# untitled.net
KiCad netlist of a schematic drawn in EAGLE
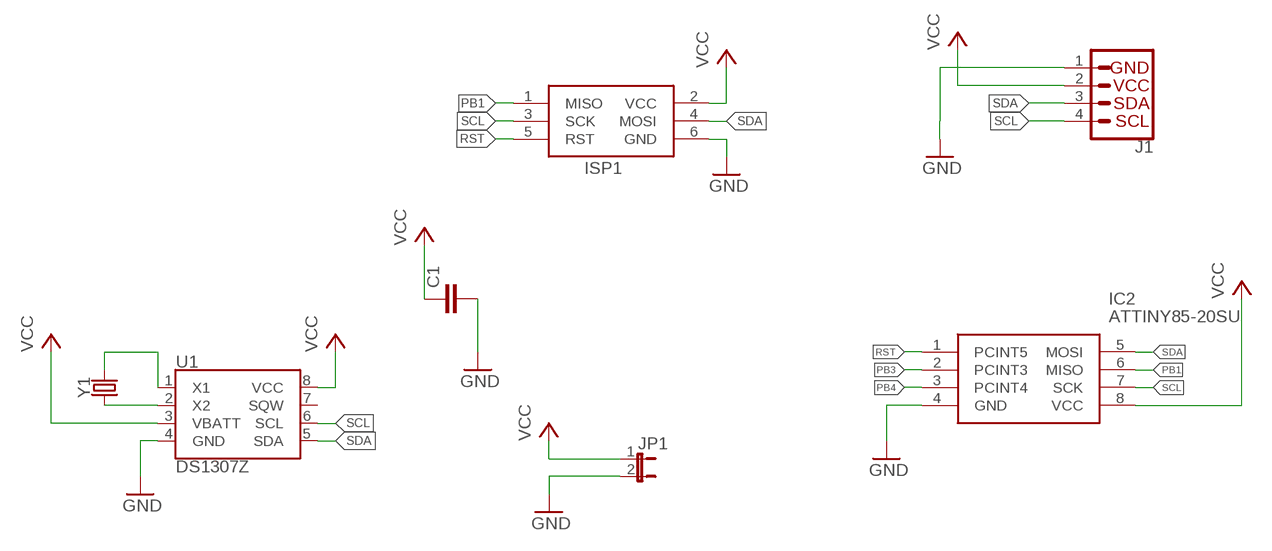
[diagram p0: schematic, sheet 1]

(export (version "E")
  (design (tool "Eeschema 10.0.6"))
  (components
    (comp (ref "C1")
      (value "C-EUC1206")
      (footprint "eagle-import:C1206")
      (libsource (lib "eagle-import") (part "C-EUC1206"))
    )
    (comp (ref "IC2")
      (value "ATTINY85-20SU")
      (footprint "eagle-import:SOT127P798X216-8N")
      (fields
        (field (name "MOUSER_PART_NUMBER") "556-ATTINY85-20SU")
        (field (name "RS_PART_NUMBER") "1331674")
      )
      (libsource (lib "eagle-import") (part "ATTINY85-20SU"))
    )
    (comp (ref "ISP1")
      (value "AVRISP-6")
      (footprint "eagle-import:AVRISP")
      (libsource (lib "eagle-import") (part "AVRISP-6"))
    )
    (comp (ref "J1")
      (value "I2C_STANDARD")
      (footprint "eagle-import:1X04")
      (libsource (lib "eagle-import") (part "I2C_STANDARD"))
    )
    (comp (ref "JP1")
      (value "JUMPER-2-OLDPTH")
      (footprint "eagle-import:1X02")
      (libsource (lib "eagle-import") (part "JUMPER-2-OLDPTH"))
    )
    (comp (ref "U1")
      (value "DS1307Z")
      (footprint "eagle-import:SO08-0.15")
      (libsource (lib "eagle-import") (part "DS1307Z"))
    )
    (comp (ref "Y1")
      (value "CRYSTALPTH-2X6")
      (footprint "eagle-import:CRYSTAL-PTH-2X6-CYL")
      (libsource (lib "eagle-import") (part "CRYSTALPTH-2X6"))
    )
  )
  (nets
    (net (code "1") (name "GND") (class "Default")
      (node (ref "C1") (pin "2") (pinfunction "2_2") (pintype "passive"))
      (node (ref "IC2") (pin "4") (pinfunction "GND_4") (pintype "power_in"))
      (node (ref "ISP1") (pin "6") (pinfunction "GND_6") (pintype "power_in"))
      (node (ref "J1") (pin "1") (pinfunction "1_1") (pintype "power_in"))
      (node (ref "JP1") (pin "2") (pinfunction "2_2") (pintype "passive"))
      (node (ref "U1") (pin "4") (pinfunction "GND_4") (pintype "bidirectional"))
    )
    (net (code "2") (name "Net-(U1-X1)") (class "Default")
      (node (ref "U1") (pin "1") (pinfunction "X1_1") (pintype "bidirectional"))
      (node (ref "Y1") (pin "2") (pinfunction "2_2") (pintype "passive"))
    )
    (net (code "3") (name "Net-(U1-X2)") (class "Default")
      (node (ref "U1") (pin "2") (pinfunction "X2_2") (pintype "bidirectional"))
      (node (ref "Y1") (pin "1") (pinfunction "1_1") (pintype "passive"))
    )
    (net (code "4") (name "PB1") (class "Default")
      (node (ref "IC2") (pin "6") (pinfunction "MISO_6") (pintype "bidirectional"))
      (node (ref "ISP1") (pin "1") (pinfunction "MISO_1") (pintype "input"))
    )
    (net (code "5") (name "PB3") (class "Default")
      (node (ref "IC2") (pin "2") (pinfunction "PCINT3_2") (pintype "bidirectional"))
    )
    (net (code "6") (name "PB4") (class "Default")
      (node (ref "IC2") (pin "3") (pinfunction "PCINT4_3") (pintype "bidirectional"))
    )
    (net (code "7") (name "RST") (class "Default")
      (node (ref "IC2") (pin "1") (pinfunction "PCINT5_1") (pintype "bidirectional"))
      (node (ref "ISP1") (pin "5") (pinfunction "RST_5") (pintype "output"))
    )
    (net (code "8") (name "SCL") (class "Default")
      (node (ref "IC2") (pin "7") (pinfunction "SCK_7") (pintype "bidirectional"))
      (node (ref "ISP1") (pin "3") (pinfunction "SCK_3") (pintype "output"))
      (node (ref "J1") (pin "4") (pinfunction "4_4") (pintype "passive"))
      (node (ref "U1") (pin "6") (pinfunction "SCL_6") (pintype "bidirectional"))
    )
    (net (code "9") (name "SDA") (class "Default")
      (node (ref "IC2") (pin "5") (pinfunction "MOSI_5") (pintype "bidirectional"))
      (node (ref "ISP1") (pin "4") (pinfunction "MOSI_4") (pintype "output"))
      (node (ref "J1") (pin "3") (pinfunction "3_3") (pintype "passive"))
      (node (ref "U1") (pin "5") (pinfunction "SDA_5") (pintype "bidirectional"))
    )
    (net (code "10") (name "VCC") (class "Default")
      (node (ref "C1") (pin "1") (pinfunction "1_1") (pintype "passive"))
      (node (ref "IC2") (pin "8") (pinfunction "VCC_8") (pintype "power_in"))
      (node (ref "ISP1") (pin "2") (pinfunction "VCC_2") (pintype "power_in"))
      (node (ref "J1") (pin "2") (pinfunction "2_2") (pintype "power_in"))
      (node (ref "JP1") (pin "1") (pinfunction "1_1") (pintype "passive"))
      (node (ref "U1") (pin "3") (pinfunction "VBATT_3") (pintype "bidirectional"))
      (node (ref "U1") (pin "8") (pinfunction "VCC_8") (pintype "bidirectional"))
    )
    (net (code "11") (name "unconnected-(U1-SQW-Pad7)") (class "Default")
      (node (ref "U1") (pin "7") (pinfunction "SQW_7") (pintype "bidirectional"))
    )
  )
)
